# TempSensor.net
KiCad netlist of a schematic drawn in Altium Designer
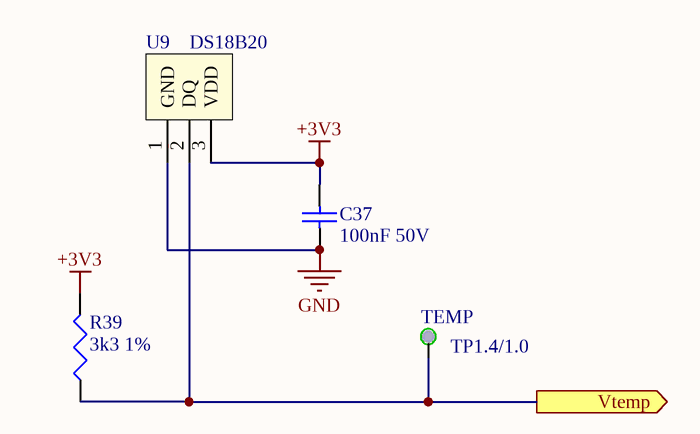
[diagram p0: TempSensor.SchDoc]

(export (version "E")
  (design (tool "Eeschema 10.0.6"))
  (components
    (comp (ref "C37")
      (value "100nF 50V")
      (footprint "IPC-7352 Chip_Capacitor_N:CAPC2012N")
      (description "Capacitor")
      (fields (field (name "PUBLISHER") "Altium Limited"))
      (libsource (lib "Miscellaneous Devices") (part "Cap Semi"))
    )
    (comp (ref "R39")
      (value "3k3 1%")
      (footprint "IPC-7352 Chip_Resistor_N:RESC2012N")
      (description "Resistor")
      (fields (field (name "PUBLISHER") "Altium Limited"))
      (libsource (lib "Miscellaneous Devices") (part "Res3"))
    )
    (comp (ref "TEMP")
      (value "TP1.4/1.0")
      (footprint "UserPcbLib:TP1.4/1.0")
      (libsource (lib "UserSchlib") (part "TP1.4/1.0"))
    )
    (comp (ref "U9")
      (value "DS18B20")
      (footprint "UserPcbLib:TO92 variant")
      (description "Digital Temperature sensor")
      (fields (field (name "MANUFACTURER") "Maxim"))
      (libsource (lib "UserSchlib") (part "DS18B20"))
    )
  )
  (nets
    (net (code "1") (name "+3V3") (class "Default")
      (node (ref "C37") (pin "2") (pinfunction "2_2") (pintype "passive"))
      (node (ref "R39") (pin "2") (pinfunction "2_2") (pintype "passive"))
      (node (ref "U9") (pin "3") (pinfunction "VDD_3") (pintype "passive"))
    )
    (net (code "2") (name "/Vtemp") (class "Default")
      (node (ref "R39") (pin "1") (pinfunction "1_1") (pintype "passive"))
      (node (ref "TEMP") (pin "1") (pinfunction "1_1") (pintype "passive"))
      (node (ref "U9") (pin "2") (pinfunction "DQ_2") (pintype "passive"))
    )
    (net (code "3") (name "GND") (class "Default")
      (node (ref "C37") (pin "1") (pinfunction "1_1") (pintype "passive"))
      (node (ref "U9") (pin "1") (pinfunction "GND_1") (pintype "passive"))
    )
  )
)
